# sa_dsp.net
KiCad netlist of a schematic drawn in EAGLE
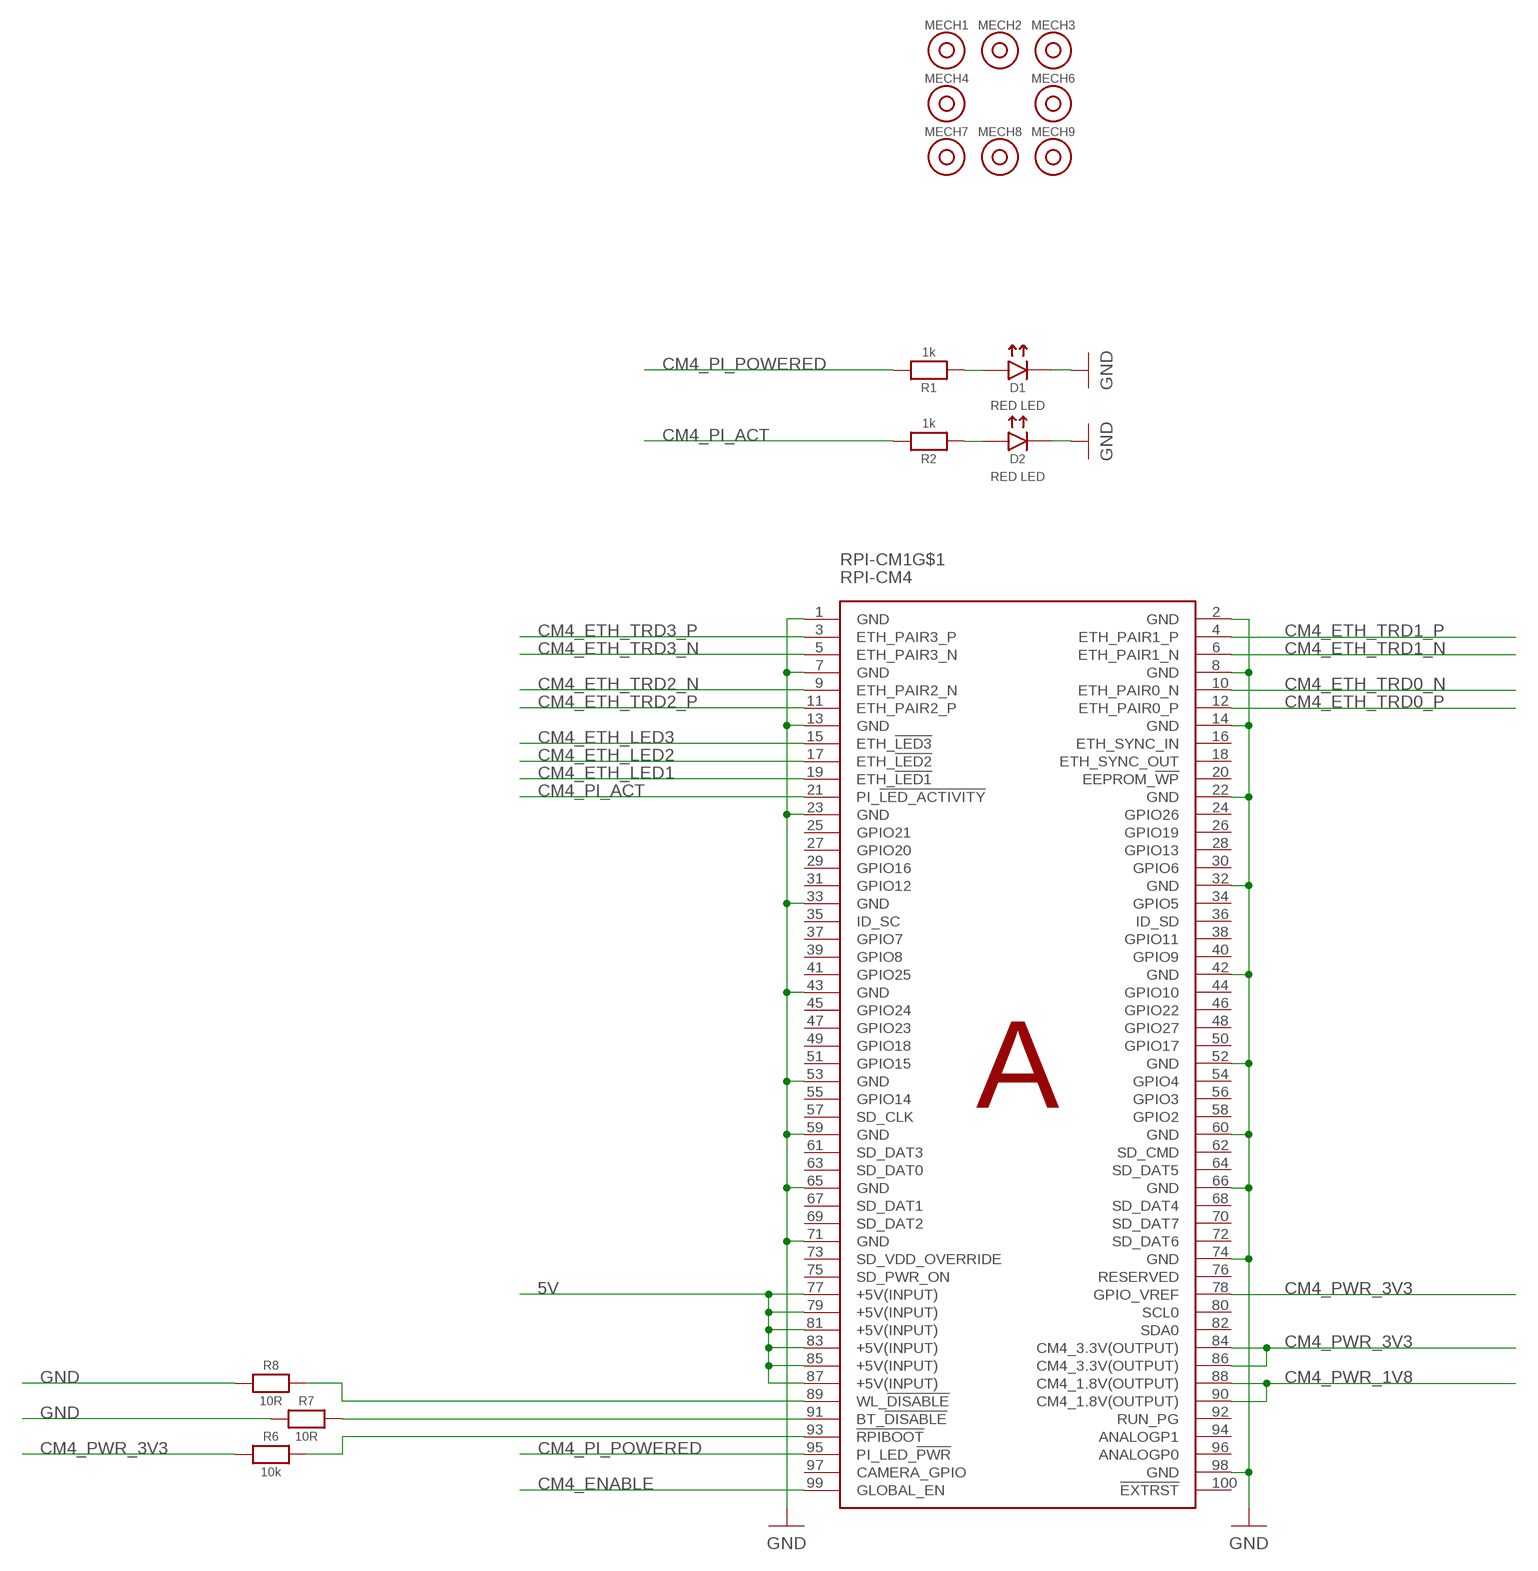
[diagram p0: schematic, sheet 1, part 1 of 2]
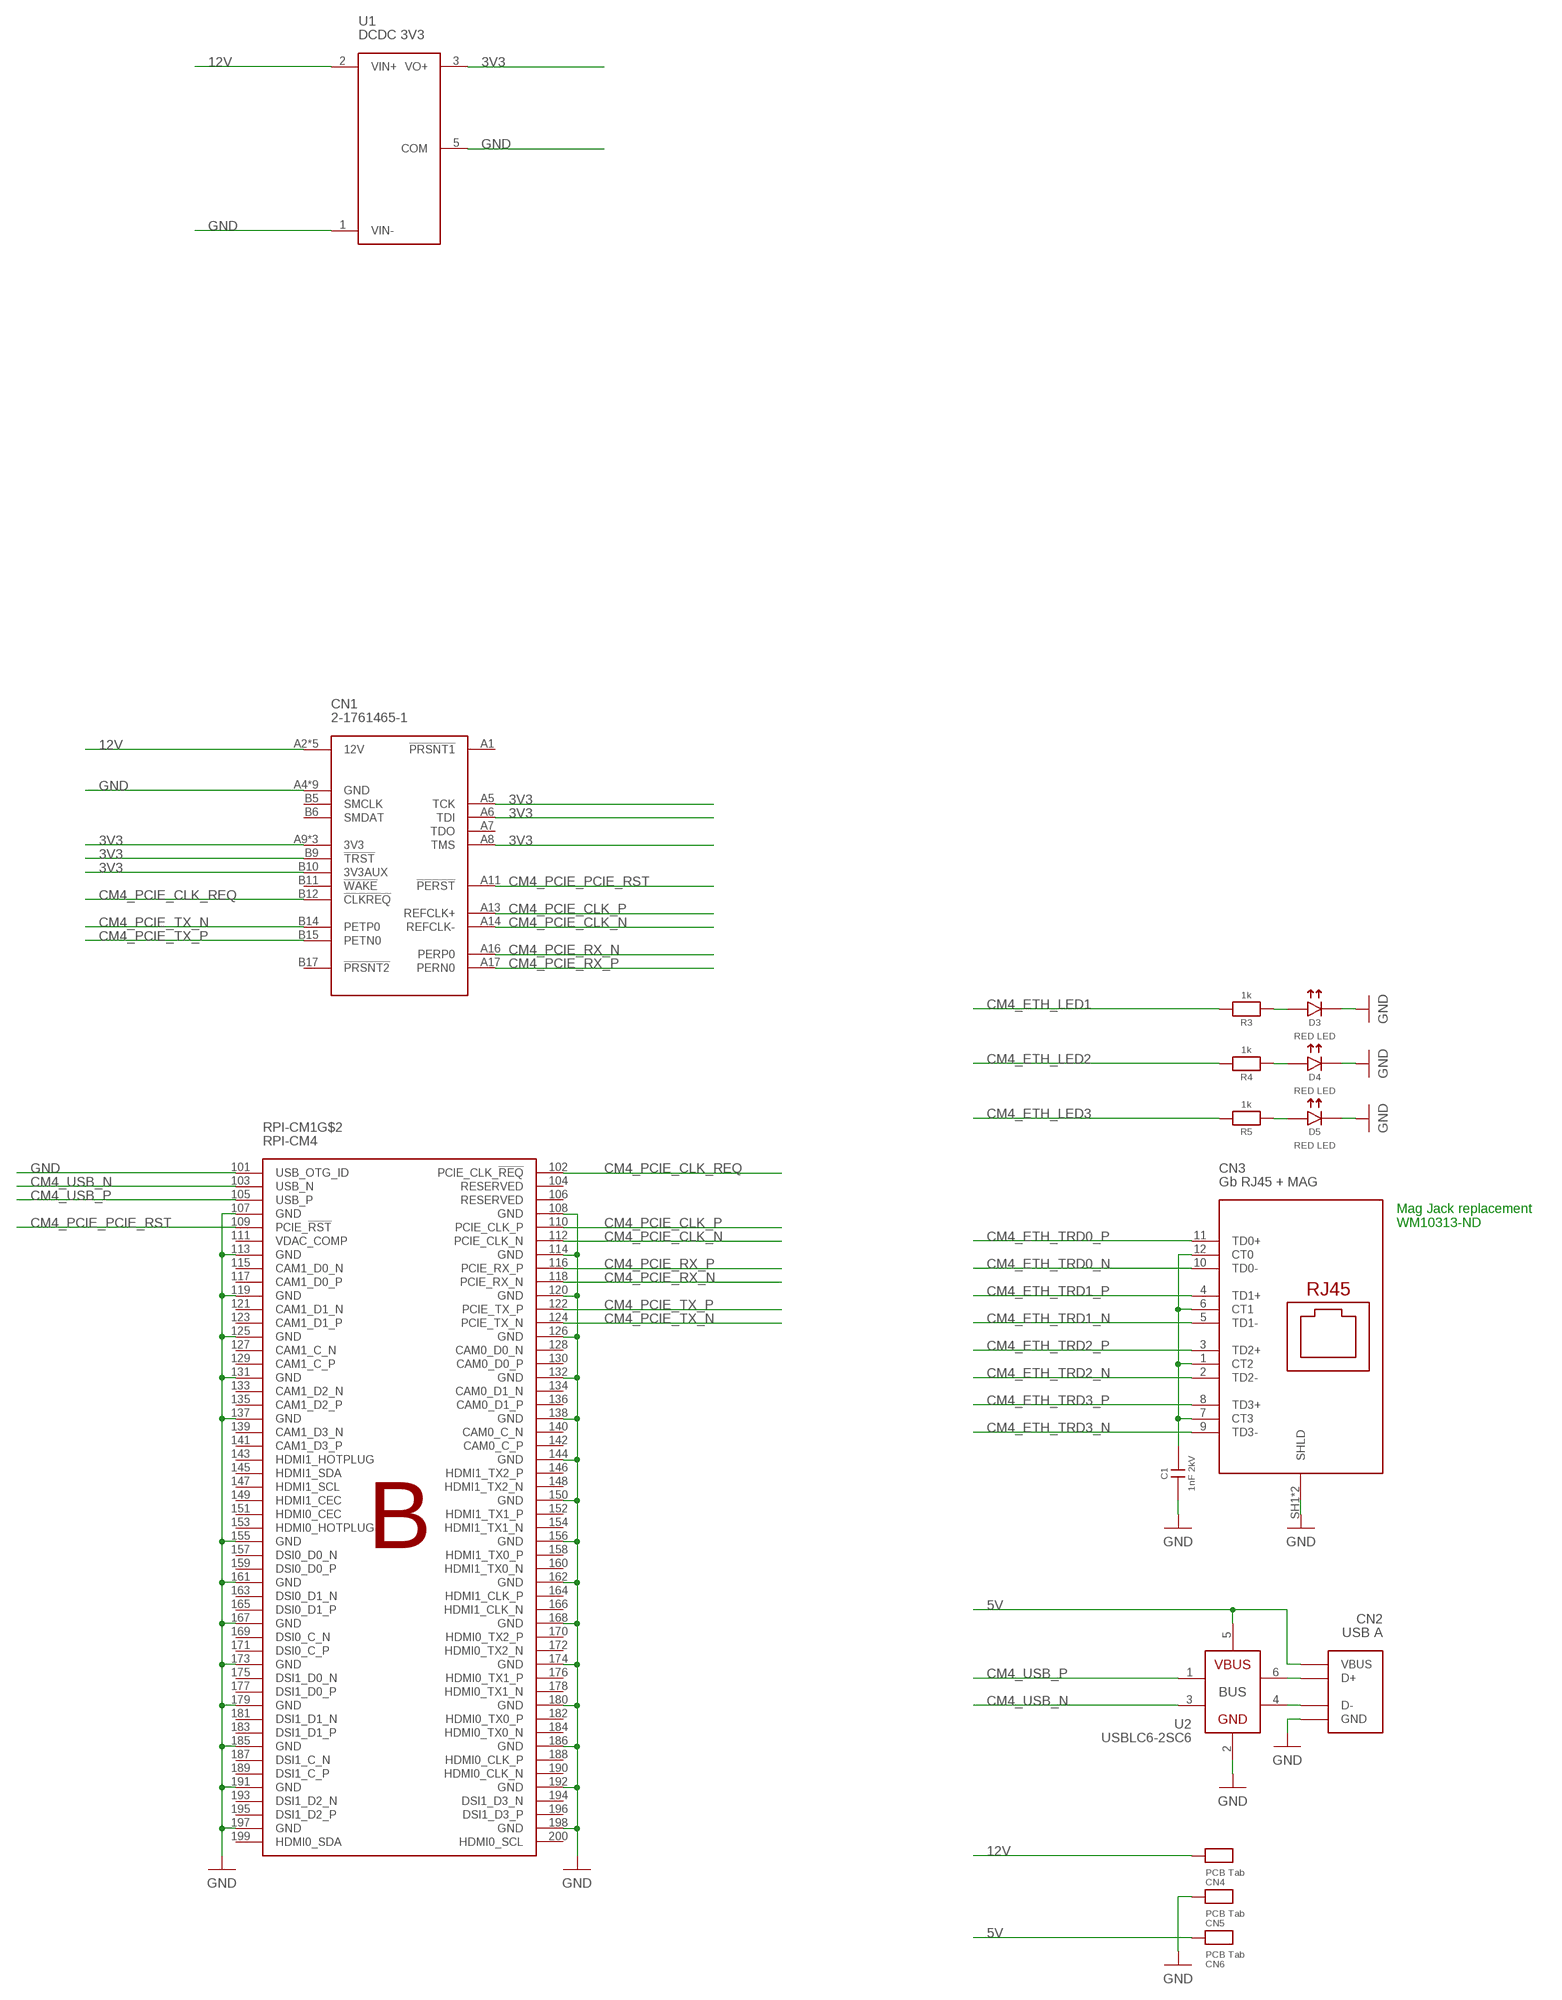
[diagram p1: schematic, sheet 1, part 2 of 2]

(export (version "E")
  (design (tool "Eeschema 10.0.6"))
  (components
    (comp (ref "C1")
      (value "1nF 2kV")
      (footprint "eagle-import:1812")
      (libsource (lib "eagle-import") (part "C1812C102KGRACAUTO"))
    )
    (comp (ref "CN1")
      (value "2-1761465-1")
      (footprint "eagle-import:CONN36_2-1761465-1_TEC")
      (libsource (lib "eagle-import") (part "2-1761465-1"))
    )
    (comp (ref "CN2")
      (value "USB A")
      (footprint "eagle-import:629104190121")
      (libsource (lib "eagle-import") (part "629104190121"))
    )
    (comp (ref "CN3")
      (value "Gb RJ45 + MAG")
      (footprint "eagle-import:0857931020")
      (libsource (lib "eagle-import") (part "0857931020"))
    )
    (comp (ref "CN4")
      (value "PCB Tab")
      (footprint "eagle-import:PCB_TAB_SMALL")
      (libsource (lib "eagle-import") (part "PCB_TAB_SMALL"))
    )
    (comp (ref "CN5")
      (value "PCB Tab")
      (footprint "eagle-import:PCB_TAB_SMALL")
      (libsource (lib "eagle-import") (part "PCB_TAB_SMALL"))
    )
    (comp (ref "CN6")
      (value "PCB Tab")
      (footprint "eagle-import:PCB_TAB_SMALL")
      (libsource (lib "eagle-import") (part "PCB_TAB_SMALL"))
    )
    (comp (ref "D1")
      (value "RED LED")
      (footprint "eagle-import:0603_POLAR")
      (libsource (lib "eagle-import") (part "150060RS75000"))
    )
    (comp (ref "D2")
      (value "RED LED")
      (footprint "eagle-import:0603_POLAR")
      (libsource (lib "eagle-import") (part "150060RS75000"))
    )
    (comp (ref "D3")
      (value "RED LED")
      (footprint "eagle-import:0603_POLAR")
      (libsource (lib "eagle-import") (part "150060RS75000"))
    )
    (comp (ref "D4")
      (value "RED LED")
      (footprint "eagle-import:0603_POLAR")
      (libsource (lib "eagle-import") (part "150060RS75000"))
    )
    (comp (ref "D5")
      (value "RED LED")
      (footprint "eagle-import:0603_POLAR")
      (libsource (lib "eagle-import") (part "150060RS75000"))
    )
    (comp (ref "MECH1")
      (value "6mm x 3mm")
      (footprint "eagle-import:MOUNTHOLE_6X3")
      (libsource (lib "eagle-import") (part "MOUNTHOLE"))
    )
    (comp (ref "MECH2")
      (value "6mm x 3mm")
      (footprint "eagle-import:MOUNTHOLE_6X3")
      (libsource (lib "eagle-import") (part "MOUNTHOLE"))
    )
    (comp (ref "MECH3")
      (value "6mm x 3mm")
      (footprint "eagle-import:MOUNTHOLE_6X3")
      (libsource (lib "eagle-import") (part "MOUNTHOLE"))
    )
    (comp (ref "MECH4")
      (value "6mm x 3mm")
      (footprint "eagle-import:MOUNTHOLE_6X3")
      (libsource (lib "eagle-import") (part "MOUNTHOLE"))
    )
    (comp (ref "MECH6")
      (value "6mm x 3mm")
      (footprint "eagle-import:MOUNTHOLE_6X3")
      (libsource (lib "eagle-import") (part "MOUNTHOLE"))
    )
    (comp (ref "MECH7")
      (value "6mm x 3mm")
      (footprint "eagle-import:MOUNTHOLE_6X3")
      (libsource (lib "eagle-import") (part "MOUNTHOLE"))
    )
    (comp (ref "MECH8")
      (value "6mm x 3mm")
      (footprint "eagle-import:MOUNTHOLE_6X3")
      (libsource (lib "eagle-import") (part "MOUNTHOLE"))
    )
    (comp (ref "MECH9")
      (value "6mm x 3mm")
      (footprint "eagle-import:MOUNTHOLE_6X3")
      (libsource (lib "eagle-import") (part "MOUNTHOLE"))
    )
    (comp (ref "R1")
      (value "1k")
      (footprint "eagle-import:0603")
      (fields
        (field (name "MANUFACTURER") "Vishay Dale")
        (field (name "POWER") "0.1W, 1/10W")
        (field (name "TOLERANCE") "±1%")
      )
      (libsource (lib "eagle-import") (part "CRCW06031K00FKEB"))
    )
    (comp (ref "R2")
      (value "1k")
      (footprint "eagle-import:0603")
      (fields
        (field (name "MANUFACTURER") "Vishay Dale")
        (field (name "POWER") "0.1W, 1/10W")
        (field (name "TOLERANCE") "±1%")
      )
      (libsource (lib "eagle-import") (part "CRCW06031K00FKEB"))
    )
    (comp (ref "R3")
      (value "1k")
      (footprint "eagle-import:0603")
      (fields
        (field (name "MANUFACTURER") "Vishay Dale")
        (field (name "POWER") "0.1W, 1/10W")
        (field (name "TOLERANCE") "±1%")
      )
      (libsource (lib "eagle-import") (part "CRCW06031K00FKEB"))
    )
    (comp (ref "R4")
      (value "1k")
      (footprint "eagle-import:0603")
      (fields
        (field (name "MANUFACTURER") "Vishay Dale")
        (field (name "POWER") "0.1W, 1/10W")
        (field (name "TOLERANCE") "±1%")
      )
      (libsource (lib "eagle-import") (part "CRCW06031K00FKEB"))
    )
    (comp (ref "R5")
      (value "1k")
      (footprint "eagle-import:0603")
      (fields
        (field (name "MANUFACTURER") "Vishay Dale")
        (field (name "POWER") "0.1W, 1/10W")
        (field (name "TOLERANCE") "±1%")
      )
      (libsource (lib "eagle-import") (part "CRCW06031K00FKEB"))
    )
    (comp (ref "R6")
      (value "10k")
      (footprint "eagle-import:0603")
      (fields
        (field (name "MANUFACTURER") "Vishay Dale")
        (field (name "POWER") "0.1W, 1/10W")
        (field (name "TOLERANCE") "±1%")
      )
      (libsource (lib "eagle-import") (part "CRCW060310K0FKTA"))
    )
    (comp (ref "R7")
      (value "10R")
      (footprint "eagle-import:0603")
      (fields
        (field (name "MANUFACTURER") "Vishay Dale")
        (field (name "POWER") "0.1W, 1/10W")
        (field (name "TOLERANCE") "±1%")
      )
      (libsource (lib "eagle-import") (part "CRCW060310R0FKTA"))
    )
    (comp (ref "R8")
      (value "10R")
      (footprint "eagle-import:0603")
      (fields
        (field (name "MANUFACTURER") "Vishay Dale")
        (field (name "POWER") "0.1W, 1/10W")
        (field (name "TOLERANCE") "±1%")
      )
      (libsource (lib "eagle-import") (part "CRCW060310R0FKTA"))
    )
    (comp (ref "RPI-CM1")
      (value "RPI-CM4")
      (footprint "eagle-import:RPI-CM4")
      (libsource (lib "eagle-import") (part "RPI-CM4"))
    )
    (comp (ref "U1")
      (value "DCDC 3V3")
      (footprint "eagle-import:PDQE10")
      (libsource (lib "eagle-import") (part "PDQE15-Q24-S3-D"))
    )
    (comp (ref "U2")
      (value "USBLC6-2SC6")
      (footprint "eagle-import:SOT23-6")
      (libsource (lib "eagle-import") (part "USBLC6-2SC6"))
    )
  )
  (nets
    (net (code "1") (name "/3V3") (class "Default")
      (node (ref "CN1") (pin "A10") (pinfunction "3V3_A10") (pintype "passive"))
      (node (ref "CN1") (pin "A5") (pinfunction "TCK_A5") (pintype "passive"))
      (node (ref "CN1") (pin "A6") (pinfunction "TDI_A6") (pintype "passive"))
      (node (ref "CN1") (pin "A8") (pinfunction "TMS_A8") (pintype "passive"))
      (node (ref "CN1") (pin "A9") (pinfunction "3V3_A9") (pintype "passive"))
      (node (ref "CN1") (pin "B10") (pinfunction "3V3AUX_B10") (pintype "passive"))
      (node (ref "CN1") (pin "B8") (pinfunction "3V3_B8") (pintype "passive"))
      (node (ref "CN1") (pin "B9") (pinfunction "~{TRST}_B9") (pintype "passive"))
      (node (ref "U1") (pin "3") (pinfunction "VO+_3") (pintype "bidirectional"))
    )
    (net (code "2") (name "/5V") (class "Default")
      (node (ref "CN2") (pin "1") (pinfunction "VBUS_1") (pintype "bidirectional"))
      (node (ref "CN6") (pin "1") (pinfunction "1_1") (pintype "bidirectional"))
      (node (ref "RPI-CM1") (pin "77") (pinfunction "+5V(INPUT)_77") (pintype "passive"))
      (node (ref "RPI-CM1") (pin "79") (pinfunction "+5V(INPUT)_79") (pintype "passive"))
      (node (ref "RPI-CM1") (pin "81") (pinfunction "+5V(INPUT)_81") (pintype "passive"))
      (node (ref "RPI-CM1") (pin "83") (pinfunction "+5V(INPUT)_83") (pintype "passive"))
      (node (ref "RPI-CM1") (pin "85") (pinfunction "+5V(INPUT)_85") (pintype "passive"))
      (node (ref "RPI-CM1") (pin "87") (pinfunction "+5V(INPUT)_87") (pintype "passive"))
      (node (ref "U2") (pin "5") (pinfunction "VBUS_5") (pintype "bidirectional"))
    )
    (net (code "3") (name "/12V") (class "Default")
      (node (ref "CN1") (pin "A2") (pinfunction "12V_A2") (pintype "passive"))
      (node (ref "CN1") (pin "A3") (pinfunction "12V_A3") (pintype "passive"))
      (node (ref "CN1") (pin "B1") (pinfunction "12V_B1") (pintype "passive"))
      (node (ref "CN1") (pin "B2") (pinfunction "12V_B2") (pintype "passive"))
      (node (ref "CN1") (pin "B3") (pinfunction "12V_B3") (pintype "passive"))
      (node (ref "CN4") (pin "1") (pinfunction "1_1") (pintype "bidirectional"))
      (node (ref "U1") (pin "2") (pinfunction "VIN+_2") (pintype "bidirectional"))
    )
    (net (code "4") (name "/CM4_ENABLE") (class "Default")
      (node (ref "RPI-CM1") (pin "99") (pinfunction "GLOBAL_EN_99") (pintype "passive"))
    )
    (net (code "5") (name "/CM4_ETH_LED1") (class "Default")
      (node (ref "R3") (pin "2") (pinfunction "2_2") (pintype "bidirectional"))
      (node (ref "RPI-CM1") (pin "19") (pinfunction "ETH_~{LED1}_19") (pintype "passive"))
    )
    (net (code "6") (name "/CM4_ETH_LED2") (class "Default")
      (node (ref "R4") (pin "2") (pinfunction "2_2") (pintype "bidirectional"))
      (node (ref "RPI-CM1") (pin "17") (pinfunction "ETH_~{LED2}_17") (pintype "passive"))
    )
    (net (code "7") (name "/CM4_ETH_LED3") (class "Default")
      (node (ref "R5") (pin "2") (pinfunction "2_2") (pintype "bidirectional"))
      (node (ref "RPI-CM1") (pin "15") (pinfunction "ETH_~{LED3}_15") (pintype "passive"))
    )
    (net (code "8") (name "/CM4_ETH_TRD0_N") (class "Default")
      (node (ref "CN3") (pin "10") (pinfunction "TD0-_10") (pintype "bidirectional"))
      (node (ref "RPI-CM1") (pin "10") (pinfunction "ETH_PAIR0_N_10") (pintype "passive"))
    )
    (net (code "9") (name "/CM4_ETH_TRD0_P") (class "Default")
      (node (ref "CN3") (pin "11") (pinfunction "TD0+_11") (pintype "bidirectional"))
      (node (ref "RPI-CM1") (pin "12") (pinfunction "ETH_PAIR0_P_12") (pintype "passive"))
    )
    (net (code "10") (name "/CM4_ETH_TRD1_N") (class "Default")
      (node (ref "CN3") (pin "5") (pinfunction "TD1-_5") (pintype "bidirectional"))
      (node (ref "RPI-CM1") (pin "6") (pinfunction "ETH_PAIR1_N_6") (pintype "passive"))
    )
    (net (code "11") (name "/CM4_ETH_TRD1_P") (class "Default")
      (node (ref "CN3") (pin "4") (pinfunction "TD1+_4") (pintype "bidirectional"))
      (node (ref "RPI-CM1") (pin "4") (pinfunction "ETH_PAIR1_P_4") (pintype "passive"))
    )
    (net (code "12") (name "/CM4_ETH_TRD2_N") (class "Default")
      (node (ref "CN3") (pin "2") (pinfunction "TD2-_2") (pintype "bidirectional"))
      (node (ref "RPI-CM1") (pin "9") (pinfunction "ETH_PAIR2_N_9") (pintype "passive"))
    )
    (net (code "13") (name "/CM4_ETH_TRD2_P") (class "Default")
      (node (ref "CN3") (pin "3") (pinfunction "TD2+_3") (pintype "bidirectional"))
      (node (ref "RPI-CM1") (pin "11") (pinfunction "ETH_PAIR2_P_11") (pintype "passive"))
    )
    (net (code "14") (name "/CM4_ETH_TRD3_N") (class "Default")
      (node (ref "CN3") (pin "9") (pinfunction "TD3-_9") (pintype "bidirectional"))
      (node (ref "RPI-CM1") (pin "5") (pinfunction "ETH_PAIR3_N_5") (pintype "passive"))
    )
    (net (code "15") (name "/CM4_ETH_TRD3_P") (class "Default")
      (node (ref "CN3") (pin "8") (pinfunction "TD3+_8") (pintype "bidirectional"))
      (node (ref "RPI-CM1") (pin "3") (pinfunction "ETH_PAIR3_P_3") (pintype "passive"))
    )
    (net (code "16") (name "/CM4_PCIE_CLK_N") (class "Default")
      (node (ref "CN1") (pin "A14") (pinfunction "REFCLK-_A14") (pintype "passive"))
      (node (ref "RPI-CM1") (pin "112") (pinfunction "PCIE_CLK_N_112") (pintype "passive"))
    )
    (net (code "17") (name "/CM4_PCIE_CLK_P") (class "Default")
      (node (ref "CN1") (pin "A13") (pinfunction "REFCLK+_A13") (pintype "passive"))
      (node (ref "RPI-CM1") (pin "110") (pinfunction "PCIE_CLK_P_110") (pintype "passive"))
    )
    (net (code "18") (name "/CM4_PCIE_CLK_REQ") (class "Default")
      (node (ref "CN1") (pin "B12") (pinfunction "~{CLKREQ}_B12") (pintype "passive"))
      (node (ref "RPI-CM1") (pin "102") (pinfunction "PCIE_CLK_~{REQ}_102") (pintype "passive"))
    )
    (net (code "19") (name "/CM4_PCIE_PCIE_RST") (class "Default")
      (node (ref "CN1") (pin "A11") (pinfunction "~{PERST}_A11") (pintype "passive"))
      (node (ref "RPI-CM1") (pin "109") (pinfunction "PCIE_~{RST}_109") (pintype "passive"))
    )
    (net (code "20") (name "/CM4_PCIE_RX_N") (class "Default")
      (node (ref "CN1") (pin "A16") (pinfunction "PERP0_A16") (pintype "passive"))
      (node (ref "RPI-CM1") (pin "118") (pinfunction "PCIE_RX_N_118") (pintype "passive"))
    )
    (net (code "21") (name "/CM4_PCIE_RX_P") (class "Default")
      (node (ref "CN1") (pin "A17") (pinfunction "PERN0_A17") (pintype "passive"))
      (node (ref "RPI-CM1") (pin "116") (pinfunction "PCIE_RX_P_116") (pintype "passive"))
    )
    (net (code "22") (name "/CM4_PCIE_TX_N") (class "Default")
      (node (ref "CN1") (pin "B14") (pinfunction "PETP0_B14") (pintype "passive"))
      (node (ref "RPI-CM1") (pin "124") (pinfunction "PCIE_TX_N_124") (pintype "passive"))
    )
    (net (code "23") (name "/CM4_PCIE_TX_P") (class "Default")
      (node (ref "CN1") (pin "B15") (pinfunction "PETN0_B15") (pintype "passive"))
      (node (ref "RPI-CM1") (pin "122") (pinfunction "PCIE_TX_P_122") (pintype "passive"))
    )
    (net (code "24") (name "/CM4_PI_ACT") (class "Default")
      (node (ref "R2") (pin "2") (pinfunction "2_2") (pintype "bidirectional"))
      (node (ref "RPI-CM1") (pin "21") (pinfunction "PI_~{LED_ACTIVITY}_21") (pintype "passive"))
    )
    (net (code "25") (name "/CM4_PI_POWERED") (class "Default")
      (node (ref "R1") (pin "2") (pinfunction "2_2") (pintype "bidirectional"))
      (node (ref "RPI-CM1") (pin "95") (pinfunction "PI_LED_~{PWR}_95") (pintype "passive"))
    )
    (net (code "26") (name "/CM4_PWR_1V8") (class "Default")
      (node (ref "RPI-CM1") (pin "88") (pinfunction "CM4_1.8V(OUTPUT)_88") (pintype "passive"))
      (node (ref "RPI-CM1") (pin "90") (pinfunction "CM4_1.8V(OUTPUT)_90") (pintype "passive"))
    )
    (net (code "27") (name "/CM4_PWR_3V3") (class "Default")
      (node (ref "R6") (pin "1") (pinfunction "1_1") (pintype "bidirectional"))
      (node (ref "RPI-CM1") (pin "78") (pinfunction "GPIO_VREF_78") (pintype "passive"))
      (node (ref "RPI-CM1") (pin "84") (pinfunction "CM4_3.3V(OUTPUT)_84") (pintype "passive"))
      (node (ref "RPI-CM1") (pin "86") (pinfunction "CM4_3.3V(OUTPUT)_86") (pintype "passive"))
    )
    (net (code "28") (name "/CM4_USB_N") (class "Default")
      (node (ref "RPI-CM1") (pin "103") (pinfunction "USB_N_103") (pintype "passive"))
      (node (ref "U2") (pin "3") (pinfunction "D-_IN_3") (pintype "bidirectional"))
    )
    (net (code "29") (name "/CM4_USB_P") (class "Default")
      (node (ref "RPI-CM1") (pin "105") (pinfunction "USB_P_105") (pintype "passive"))
      (node (ref "U2") (pin "1") (pinfunction "D+_IN_1") (pintype "bidirectional"))
    )
    (net (code "30") (name "GND") (class "Default")
      (node (ref "C1") (pin "1") (pinfunction "1_1") (pintype "bidirectional"))
      (node (ref "CN1") (pin "A12") (pinfunction "GND_A12") (pintype "passive"))
      (node (ref "CN1") (pin "A15") (pinfunction "GND_A15") (pintype "passive"))
      (node (ref "CN1") (pin "A18") (pinfunction "GND_A18") (pintype "passive"))
      (node (ref "CN1") (pin "A4") (pinfunction "GND_A4") (pintype "passive"))
      (node (ref "CN1") (pin "B13") (pinfunction "GND_B13") (pintype "passive"))
      (node (ref "CN1") (pin "B16") (pinfunction "GND_B16") (pintype "passive"))
      (node (ref "CN1") (pin "B18") (pinfunction "GND_B18") (pintype "passive"))
      (node (ref "CN1") (pin "B4") (pinfunction "GND_B4") (pintype "passive"))
      (node (ref "CN1") (pin "B7") (pinfunction "GND_B7") (pintype "passive"))
      (node (ref "CN2") (pin "4") (pinfunction "GND_4") (pintype "bidirectional"))
      (node (ref "CN2") (pin "SH1") (pinfunction "GND_SH1") (pintype "bidirectional"))
      (node (ref "CN2") (pin "SH2") (pinfunction "GND_SH2") (pintype "bidirectional"))
      (node (ref "CN2") (pin "SH3") (pinfunction "GND_SH3") (pintype "bidirectional"))
      (node (ref "CN2") (pin "SH4") (pinfunction "GND_SH4") (pintype "bidirectional"))
      (node (ref "CN3") (pin "SH1") (pinfunction "SHLD_SH1") (pintype "bidirectional"))
      (node (ref "CN3") (pin "SH2") (pinfunction "SHLD_SH2") (pintype "bidirectional"))
      (node (ref "CN5") (pin "1") (pinfunction "1_1") (pintype "bidirectional"))
      (node (ref "D1") (pin "K") (pinfunction "K_K") (pintype "bidirectional"))
      (node (ref "D2") (pin "K") (pinfunction "K_K") (pintype "bidirectional"))
      (node (ref "D3") (pin "K") (pinfunction "K_K") (pintype "bidirectional"))
      (node (ref "D4") (pin "K") (pinfunction "K_K") (pintype "bidirectional"))
      (node (ref "D5") (pin "K") (pinfunction "K_K") (pintype "bidirectional"))
      (node (ref "R7") (pin "1") (pinfunction "1_1") (pintype "bidirectional"))
      (node (ref "R8") (pin "1") (pinfunction "1_1") (pintype "bidirectional"))
      (node (ref "RPI-CM1") (pin "1") (pinfunction "GND_1") (pintype "passive"))
      (node (ref "RPI-CM1") (pin "101") (pinfunction "USB_OTG_ID_101") (pintype "passive"))
      (node (ref "RPI-CM1") (pin "107") (pinfunction "GND_107") (pintype "passive"))
      (node (ref "RPI-CM1") (pin "108") (pinfunction "GND_108") (pintype "passive"))
      (node (ref "RPI-CM1") (pin "113") (pinfunction "GND_113") (pintype "passive"))
      (node (ref "RPI-CM1") (pin "114") (pinfunction "GND_114") (pintype "passive"))
      (node (ref "RPI-CM1") (pin "119") (pinfunction "GND_119") (pintype "passive"))
      (node (ref "RPI-CM1") (pin "120") (pinfunction "GND_120") (pintype "passive"))
      (node (ref "RPI-CM1") (pin "125") (pinfunction "GND_125") (pintype "passive"))
      (node (ref "RPI-CM1") (pin "126") (pinfunction "GND_126") (pintype "passive"))
      (node (ref "RPI-CM1") (pin "13") (pinfunction "GND_13") (pintype "passive"))
      (node (ref "RPI-CM1") (pin "131") (pinfunction "GND_131") (pintype "passive"))
      (node (ref "RPI-CM1") (pin "132") (pinfunction "GND_132") (pintype "passive"))
      (node (ref "RPI-CM1") (pin "137") (pinfunction "GND_137") (pintype "passive"))
      (node (ref "RPI-CM1") (pin "138") (pinfunction "GND_138") (pintype "passive"))
      (node (ref "RPI-CM1") (pin "14") (pinfunction "GND_14") (pintype "passive"))
      (node (ref "RPI-CM1") (pin "144") (pinfunction "GND_144") (pintype "passive"))
      (node (ref "RPI-CM1") (pin "150") (pinfunction "GND_150") (pintype "passive"))
      (node (ref "RPI-CM1") (pin "155") (pinfunction "GND_155") (pintype "passive"))
      (node (ref "RPI-CM1") (pin "156") (pinfunction "GND_156") (pintype "passive"))
      (node (ref "RPI-CM1") (pin "161") (pinfunction "GND_161") (pintype "passive"))
      (node (ref "RPI-CM1") (pin "162") (pinfunction "GND_162") (pintype "passive"))
      (node (ref "RPI-CM1") (pin "167") (pinfunction "GND_167") (pintype "passive"))
      (node (ref "RPI-CM1") (pin "168") (pinfunction "GND_168") (pintype "passive"))
      (node (ref "RPI-CM1") (pin "173") (pinfunction "GND_173") (pintype "passive"))
      (node (ref "RPI-CM1") (pin "174") (pinfunction "GND_174") (pintype "passive"))
      (node (ref "RPI-CM1") (pin "179") (pinfunction "GND_179") (pintype "passive"))
      (node (ref "RPI-CM1") (pin "180") (pinfunction "GND_180") (pintype "passive"))
      (node (ref "RPI-CM1") (pin "185") (pinfunction "GND_185") (pintype "passive"))
      (node (ref "RPI-CM1") (pin "186") (pinfunction "GND_186") (pintype "passive"))
      (node (ref "RPI-CM1") (pin "191") (pinfunction "GND_191") (pintype "passive"))
      (node (ref "RPI-CM1") (pin "192") (pinfunction "GND_192") (pintype "passive"))
      (node (ref "RPI-CM1") (pin "197") (pinfunction "GND_197") (pintype "passive"))
      (node (ref "RPI-CM1") (pin "198") (pinfunction "GND_198") (pintype "passive"))
      (node (ref "RPI-CM1") (pin "2") (pinfunction "GND_2") (pintype "passive"))
      (node (ref "RPI-CM1") (pin "22") (pinfunction "GND_22") (pintype "passive"))
      (node (ref "RPI-CM1") (pin "23") (pinfunction "GND_23") (pintype "passive"))
      (node (ref "RPI-CM1") (pin "32") (pinfunction "GND_32") (pintype "passive"))
      (node (ref "RPI-CM1") (pin "33") (pinfunction "GND_33") (pintype "passive"))
      (node (ref "RPI-CM1") (pin "42") (pinfunction "GND_42") (pintype "passive"))
      (node (ref "RPI-CM1") (pin "43") (pinfunction "GND_43") (pintype "passive"))
      (node (ref "RPI-CM1") (pin "52") (pinfunction "GND_52") (pintype "passive"))
      (node (ref "RPI-CM1") (pin "53") (pinfunction "GND_53") (pintype "passive"))
      (node (ref "RPI-CM1") (pin "59") (pinfunction "GND_59") (pintype "passive"))
      (node (ref "RPI-CM1") (pin "60") (pinfunction "GND_60") (pintype "passive"))
      (node (ref "RPI-CM1") (pin "65") (pinfunction "GND_65") (pintype "passive"))
      (node (ref "RPI-CM1") (pin "66") (pinfunction "GND_66") (pintype "passive"))
      (node (ref "RPI-CM1") (pin "7") (pinfunction "GND_7") (pintype "passive"))
      (node (ref "RPI-CM1") (pin "71") (pinfunction "GND_71") (pintype "passive"))
      (node (ref "RPI-CM1") (pin "74") (pinfunction "GND_74") (pintype "passive"))
      (node (ref "RPI-CM1") (pin "8") (pinfunction "GND_8") (pintype "passive"))
      (node (ref "RPI-CM1") (pin "98") (pinfunction "GND_98") (pintype "passive"))
      (node (ref "U1") (pin "1") (pinfunction "VIN-_1") (pintype "bidirectional"))
      (node (ref "U1") (pin "5") (pinfunction "COM_5") (pintype "bidirectional"))
      (node (ref "U2") (pin "2") (pinfunction "GND_2") (pintype "bidirectional"))
    )
    (net (code "31") (name "Net-(CN2-D+)") (class "Default")
      (node (ref "CN2") (pin "3") (pinfunction "D+_3") (pintype "bidirectional"))
      (node (ref "U2") (pin "6") (pinfunction "D+_OUT_6") (pintype "bidirectional"))
    )
    (net (code "32") (name "Net-(CN2-D-)") (class "Default")
      (node (ref "CN2") (pin "2") (pinfunction "D-_2") (pintype "bidirectional"))
      (node (ref "U2") (pin "4") (pinfunction "D-OUT_4") (pintype "bidirectional"))
    )
    (net (code "33") (name "Net-(CN3-CT0)") (class "Default")
      (node (ref "C1") (pin "2") (pinfunction "2_2") (pintype "bidirectional"))
      (node (ref "CN3") (pin "1") (pinfunction "CT2_1") (pintype "bidirectional"))
      (node (ref "CN3") (pin "12") (pinfunction "CT0_12") (pintype "bidirectional"))
      (node (ref "CN3") (pin "6") (pinfunction "CT1_6") (pintype "bidirectional"))
      (node (ref "CN3") (pin "7") (pinfunction "CT3_7") (pintype "bidirectional"))
    )
    (net (code "34") (name "Net-(D1-PadA)") (class "Default")
      (node (ref "D1") (pin "A") (pinfunction "A_A") (pintype "bidirectional"))
      (node (ref "R1") (pin "1") (pinfunction "1_1") (pintype "bidirectional"))
    )
    (net (code "35") (name "Net-(D2-PadA)") (class "Default")
      (node (ref "D2") (pin "A") (pinfunction "A_A") (pintype "bidirectional"))
      (node (ref "R2") (pin "1") (pinfunction "1_1") (pintype "bidirectional"))
    )
    (net (code "36") (name "Net-(D3-PadA)") (class "Default")
      (node (ref "D3") (pin "A") (pinfunction "A_A") (pintype "bidirectional"))
      (node (ref "R3") (pin "1") (pinfunction "1_1") (pintype "bidirectional"))
    )
    (net (code "37") (name "Net-(D4-PadA)") (class "Default")
      (node (ref "D4") (pin "A") (pinfunction "A_A") (pintype "bidirectional"))
      (node (ref "R4") (pin "1") (pinfunction "1_1") (pintype "bidirectional"))
    )
    (net (code "38") (name "Net-(D5-PadA)") (class "Default")
      (node (ref "D5") (pin "A") (pinfunction "A_A") (pintype "bidirectional"))
      (node (ref "R5") (pin "1") (pinfunction "1_1") (pintype "bidirectional"))
    )
    (net (code "39") (name "Net-(RPI-CM1A-BT_~{DISABLE})") (class "Default")
      (node (ref "R7") (pin "2") (pinfunction "2_2") (pintype "bidirectional"))
      (node (ref "RPI-CM1") (pin "91") (pinfunction "BT_~{DISABLE}_91") (pintype "passive"))
    )
    (net (code "40") (name "Net-(RPI-CM1A-WL_~{DISABLE})") (class "Default")
      (node (ref "R8") (pin "2") (pinfunction "2_2") (pintype "bidirectional"))
      (node (ref "RPI-CM1") (pin "89") (pinfunction "WL_~{DISABLE}_89") (pintype "passive"))
    )
    (net (code "41") (name "Net-(RPI-CM1A-~{RPIBOOT})") (class "Default")
      (node (ref "R6") (pin "2") (pinfunction "2_2") (pintype "bidirectional"))
      (node (ref "RPI-CM1") (pin "93") (pinfunction "~{RPIBOOT}_93") (pintype "passive"))
    )
    (net (code "42") (name "unconnected-(CN1-SMCLK-PadB5)") (class "Default")
      (node (ref "CN1") (pin "B5") (pinfunction "SMCLK_B5") (pintype "passive"))
    )
    (net (code "43") (name "unconnected-(CN1-SMDAT-PadB6)") (class "Default")
      (node (ref "CN1") (pin "B6") (pinfunction "SMDAT_B6") (pintype "passive"))
    )
    (net (code "44") (name "unconnected-(CN1-TDO-PadA7)") (class "Default")
      (node (ref "CN1") (pin "A7") (pinfunction "TDO_A7") (pintype "passive"))
    )
    (net (code "45") (name "unconnected-(CN1-~{PRSNT1}-PadA1)") (class "Default")
      (node (ref "CN1") (pin "A1") (pinfunction "~{PRSNT1}_A1") (pintype "passive"))
    )
    (net (code "46") (name "unconnected-(CN1-~{PRSNT2}-PadB17)") (class "Default")
      (node (ref "CN1") (pin "B17") (pinfunction "~{PRSNT2}_B17") (pintype "passive"))
    )
    (net (code "47") (name "unconnected-(CN1-~{WAKE}-PadB11)") (class "Default")
      (node (ref "CN1") (pin "B11") (pinfunction "~{WAKE}_B11") (pintype "passive"))
    )
    (net (code "48") (name "unconnected-(RPI-CM1A-ANALOGP0-Pad96)") (class "Default")
      (node (ref "RPI-CM1") (pin "96") (pinfunction "ANALOGP0_96") (pintype "passive"))
    )
    (net (code "49") (name "unconnected-(RPI-CM1A-ANALOGP1-Pad94)") (class "Default")
      (node (ref "RPI-CM1") (pin "94") (pinfunction "ANALOGP1_94") (pintype "passive"))
    )
    (net (code "50") (name "unconnected-(RPI-CM1A-CAMERA_GPIO-Pad97)") (class "Default")
      (node (ref "RPI-CM1") (pin "97") (pinfunction "CAMERA_GPIO_97") (pintype "passive"))
    )
    (net (code "51") (name "unconnected-(RPI-CM1A-EEPROM_~{WP}-Pad20)") (class "Default")
      (node (ref "RPI-CM1") (pin "20") (pinfunction "EEPROM_~{WP}_20") (pintype "passive"))
    )
    (net (code "52") (name "unconnected-(RPI-CM1A-ETH_SYNC_IN-Pad16)") (class "Default")
      (node (ref "RPI-CM1") (pin "16") (pinfunction "ETH_SYNC_IN_16") (pintype "passive"))
    )
    (net (code "53") (name "unconnected-(RPI-CM1A-ETH_SYNC_OUT-Pad18)") (class "Default")
      (node (ref "RPI-CM1") (pin "18") (pinfunction "ETH_SYNC_OUT_18") (pintype "passive"))
    )
    (net (code "54") (name "unconnected-(RPI-CM1A-GPIO2-Pad58)") (class "Default")
      (node (ref "RPI-CM1") (pin "58") (pinfunction "GPIO2_58") (pintype "passive"))
    )
    (net (code "55") (name "unconnected-(RPI-CM1A-GPIO3-Pad56)") (class "Default")
      (node (ref "RPI-CM1") (pin "56") (pinfunction "GPIO3_56") (pintype "passive"))
    )
    (net (code "56") (name "unconnected-(RPI-CM1A-GPIO4-Pad54)") (class "Default")
      (node (ref "RPI-CM1") (pin "54") (pinfunction "GPIO4_54") (pintype "passive"))
    )
    (net (code "57") (name "unconnected-(RPI-CM1A-GPIO5-Pad34)") (class "Default")
      (node (ref "RPI-CM1") (pin "34") (pinfunction "GPIO5_34") (pintype "passive"))
    )
    (net (code "58") (name "unconnected-(RPI-CM1A-GPIO6-Pad30)") (class "Default")
      (node (ref "RPI-CM1") (pin "30") (pinfunction "GPIO6_30") (pintype "passive"))
    )
    (net (code "59") (name "unconnected-(RPI-CM1A-GPIO7-Pad37)") (class "Default")
      (node (ref "RPI-CM1") (pin "37") (pinfunction "GPIO7_37") (pintype "passive"))
    )
    (net (code "60") (name "unconnected-(RPI-CM1A-GPIO8-Pad39)") (class "Default")
      (node (ref "RPI-CM1") (pin "39") (pinfunction "GPIO8_39") (pintype "passive"))
    )
    (net (code "61") (name "unconnected-(RPI-CM1A-GPIO9-Pad40)") (class "Default")
      (node (ref "RPI-CM1") (pin "40") (pinfunction "GPIO9_40") (pintype "passive"))
    )
    (net (code "62") (name "unconnected-(RPI-CM1A-GPIO10-Pad44)") (class "Default")
      (node (ref "RPI-CM1") (pin "44") (pinfunction "GPIO10_44") (pintype "passive"))
    )
    (net (code "63") (name "unconnected-(RPI-CM1A-GPIO11-Pad38)") (class "Default")
      (node (ref "RPI-CM1") (pin "38") (pinfunction "GPIO11_38") (pintype "passive"))
    )
    (net (code "64") (name "unconnected-(RPI-CM1A-GPIO12-Pad31)") (class "Default")
      (node (ref "RPI-CM1") (pin "31") (pinfunction "GPIO12_31") (pintype "passive"))
    )
    (net (code "65") (name "unconnected-(RPI-CM1A-GPIO13-Pad28)") (class "Default")
      (node (ref "RPI-CM1") (pin "28") (pinfunction "GPIO13_28") (pintype "passive"))
    )
    (net (code "66") (name "unconnected-(RPI-CM1A-GPIO14-Pad55)") (class "Default")
      (node (ref "RPI-CM1") (pin "55") (pinfunction "GPIO14_55") (pintype "passive"))
    )
    (net (code "67") (name "unconnected-(RPI-CM1A-GPIO15-Pad51)") (class "Default")
      (node (ref "RPI-CM1") (pin "51") (pinfunction "GPIO15_51") (pintype "passive"))
    )
    (net (code "68") (name "unconnected-(RPI-CM1A-GPIO16-Pad29)") (class "Default")
      (node (ref "RPI-CM1") (pin "29") (pinfunction "GPIO16_29") (pintype "passive"))
    )
    (net (code "69") (name "unconnected-(RPI-CM1A-GPIO17-Pad50)") (class "Default")
      (node (ref "RPI-CM1") (pin "50") (pinfunction "GPIO17_50") (pintype "passive"))
    )
    (net (code "70") (name "unconnected-(RPI-CM1A-GPIO18-Pad49)") (class "Default")
      (node (ref "RPI-CM1") (pin "49") (pinfunction "GPIO18_49") (pintype "passive"))
    )
    (net (code "71") (name "unconnected-(RPI-CM1A-GPIO19-Pad26)") (class "Default")
      (node (ref "RPI-CM1") (pin "26") (pinfunction "GPIO19_26") (pintype "passive"))
    )
    (net (code "72") (name "unconnected-(RPI-CM1A-GPIO20-Pad27)") (class "Default")
      (node (ref "RPI-CM1") (pin "27") (pinfunction "GPIO20_27") (pintype "passive"))
    )
    (net (code "73") (name "unconnected-(RPI-CM1A-GPIO21-Pad25)") (class "Default")
      (node (ref "RPI-CM1") (pin "25") (pinfunction "GPIO21_25") (pintype "passive"))
    )
    (net (code "74") (name "unconnected-(RPI-CM1A-GPIO22-Pad46)") (class "Default")
      (node (ref "RPI-CM1") (pin "46") (pinfunction "GPIO22_46") (pintype "passive"))
    )
    (net (code "75") (name "unconnected-(RPI-CM1A-GPIO23-Pad47)") (class "Default")
      (node (ref "RPI-CM1") (pin "47") (pinfunction "GPIO23_47") (pintype "passive"))
    )
    (net (code "76") (name "unconnected-(RPI-CM1A-GPIO24-Pad45)") (class "Default")
      (node (ref "RPI-CM1") (pin "45") (pinfunction "GPIO24_45") (pintype "passive"))
    )
    (net (code "77") (name "unconnected-(RPI-CM1A-GPIO25-Pad41)") (class "Default")
      (node (ref "RPI-CM1") (pin "41") (pinfunction "GPIO25_41") (pintype "passive"))
    )
    (net (code "78") (name "unconnected-(RPI-CM1A-GPIO26-Pad24)") (class "Default")
      (node (ref "RPI-CM1") (pin "24") (pinfunction "GPIO26_24") (pintype "passive"))
    )
    (net (code "79") (name "unconnected-(RPI-CM1A-GPIO27-Pad48)") (class "Default")
      (node (ref "RPI-CM1") (pin "48") (pinfunction "GPIO27_48") (pintype "passive"))
    )
    (net (code "80") (name "unconnected-(RPI-CM1A-ID_SC-Pad35)") (class "Default")
      (node (ref "RPI-CM1") (pin "35") (pinfunction "ID_SC_35") (pintype "passive"))
    )
    (net (code "81") (name "unconnected-(RPI-CM1A-ID_SD-Pad36)") (class "Default")
      (node (ref "RPI-CM1") (pin "36") (pinfunction "ID_SD_36") (pintype "passive"))
    )
    (net (code "82") (name "unconnected-(RPI-CM1A-RESERVED-Pad76)") (class "Default")
      (node (ref "RPI-CM1") (pin "76") (pinfunction "RESERVED_76") (pintype "passive"))
    )
    (net (code "83") (name "unconnected-(RPI-CM1A-RUN_PG-Pad92)") (class "Default")
      (node (ref "RPI-CM1") (pin "92") (pinfunction "RUN_PG_92") (pintype "passive"))
    )
    (net (code "84") (name "unconnected-(RPI-CM1A-SCL0-Pad80)") (class "Default")
      (node (ref "RPI-CM1") (pin "80") (pinfunction "SCL0_80") (pintype "passive"))
    )
    (net (code "85") (name "unconnected-(RPI-CM1A-SDA0-Pad82)") (class "Default")
      (node (ref "RPI-CM1") (pin "82") (pinfunction "SDA0_82") (pintype "passive"))
    )
    (net (code "86") (name "unconnected-(RPI-CM1A-SD_CLK-Pad57)") (class "Default")
      (node (ref "RPI-CM1") (pin "57") (pinfunction "SD_CLK_57") (pintype "passive"))
    )
    (net (code "87") (name "unconnected-(RPI-CM1A-SD_CMD-Pad62)") (class "Default")
      (node (ref "RPI-CM1") (pin "62") (pinfunction "SD_CMD_62") (pintype "passive"))
    )
    (net (code "88") (name "unconnected-(RPI-CM1A-SD_DAT0-Pad63)") (class "Default")
      (node (ref "RPI-CM1") (pin "63") (pinfunction "SD_DAT0_63") (pintype "passive"))
    )
    (net (code "89") (name "unconnected-(RPI-CM1A-SD_DAT1-Pad67)") (class "Default")
      (node (ref "RPI-CM1") (pin "67") (pinfunction "SD_DAT1_67") (pintype "passive"))
    )
    (net (code "90") (name "unconnected-(RPI-CM1A-SD_DAT2-Pad69)") (class "Default")
      (node (ref "RPI-CM1") (pin "69") (pinfunction "SD_DAT2_69") (pintype "passive"))
    )
    (net (code "91") (name "unconnected-(RPI-CM1A-SD_DAT3-Pad61)") (class "Default")
      (node (ref "RPI-CM1") (pin "61") (pinfunction "SD_DAT3_61") (pintype "passive"))
    )
    (net (code "92") (name "unconnected-(RPI-CM1A-SD_DAT4-Pad68)") (class "Default")
      (node (ref "RPI-CM1") (pin "68") (pinfunction "SD_DAT4_68") (pintype "passive"))
    )
    (net (code "93") (name "unconnected-(RPI-CM1A-SD_DAT5-Pad64)") (class "Default")
      (node (ref "RPI-CM1") (pin "64") (pinfunction "SD_DAT5_64") (pintype "passive"))
    )
    (net (code "94") (name "unconnected-(RPI-CM1A-SD_DAT6-Pad72)") (class "Default")
      (node (ref "RPI-CM1") (pin "72") (pinfunction "SD_DAT6_72") (pintype "passive"))
    )
    (net (code "95") (name "unconnected-(RPI-CM1A-SD_DAT7-Pad70)") (class "Default")
      (node (ref "RPI-CM1") (pin "70") (pinfunction "SD_DAT7_70") (pintype "passive"))
    )
    (net (code "96") (name "unconnected-(RPI-CM1A-SD_PWR_ON-Pad75)") (class "Default")
      (node (ref "RPI-CM1") (pin "75") (pinfunction "SD_PWR_ON_75") (pintype "passive"))
    )
    (net (code "97") (name "unconnected-(RPI-CM1A-SD_VDD_OVERRIDE-Pad73)") (class "Default")
      (node (ref "RPI-CM1") (pin "73") (pinfunction "SD_VDD_OVERRIDE_73") (pintype "passive"))
    )
    (net (code "98") (name "unconnected-(RPI-CM1A-~{EXTRST}-Pad100)") (class "Default")
      (node (ref "RPI-CM1") (pin "100") (pinfunction "~{EXTRST}_100") (pintype "passive"))
    )
    (net (code "99") (name "unconnected-(RPI-CM1B-CAM0_C_N-Pad140)") (class "Default")
      (node (ref "RPI-CM1") (pin "140") (pinfunction "CAM0_C_N_140") (pintype "passive"))
    )
    (net (code "100") (name "unconnected-(RPI-CM1B-CAM0_C_P-Pad142)") (class "Default")
      (node (ref "RPI-CM1") (pin "142") (pinfunction "CAM0_C_P_142") (pintype "passive"))
    )
    (net (code "101") (name "unconnected-(RPI-CM1B-CAM0_D0_N-Pad128)") (class "Default")
      (node (ref "RPI-CM1") (pin "128") (pinfunction "CAM0_D0_N_128") (pintype "passive"))
    )
    (net (code "102") (name "unconnected-(RPI-CM1B-CAM0_D0_P-Pad130)") (class "Default")
      (node (ref "RPI-CM1") (pin "130") (pinfunction "CAM0_D0_P_130") (pintype "passive"))
    )
    (net (code "103") (name "unconnected-(RPI-CM1B-CAM0_D1_N-Pad134)") (class "Default")
      (node (ref "RPI-CM1") (pin "134") (pinfunction "CAM0_D1_N_134") (pintype "passive"))
    )
    (net (code "104") (name "unconnected-(RPI-CM1B-CAM0_D1_P-Pad136)") (class "Default")
      (node (ref "RPI-CM1") (pin "136") (pinfunction "CAM0_D1_P_136") (pintype "passive"))
    )
    (net (code "105") (name "unconnected-(RPI-CM1B-CAM1_C_N-Pad127)") (class "Default")
      (node (ref "RPI-CM1") (pin "127") (pinfunction "CAM1_C_N_127") (pintype "passive"))
    )
    (net (code "106") (name "unconnected-(RPI-CM1B-CAM1_C_P-Pad129)") (class "Default")
      (node (ref "RPI-CM1") (pin "129") (pinfunction "CAM1_C_P_129") (pintype "passive"))
    )
    (net (code "107") (name "unconnected-(RPI-CM1B-CAM1_D0_N-Pad115)") (class "Default")
      (node (ref "RPI-CM1") (pin "115") (pinfunction "CAM1_D0_N_115") (pintype "passive"))
    )
    (net (code "108") (name "unconnected-(RPI-CM1B-CAM1_D0_P-Pad117)") (class "Default")
      (node (ref "RPI-CM1") (pin "117") (pinfunction "CAM1_D0_P_117") (pintype "passive"))
    )
    (net (code "109") (name "unconnected-(RPI-CM1B-CAM1_D1_N-Pad121)") (class "Default")
      (node (ref "RPI-CM1") (pin "121") (pinfunction "CAM1_D1_N_121") (pintype "passive"))
    )
    (net (code "110") (name "unconnected-(RPI-CM1B-CAM1_D1_P-Pad123)") (class "Default")
      (node (ref "RPI-CM1") (pin "123") (pinfunction "CAM1_D1_P_123") (pintype "passive"))
    )
    (net (code "111") (name "unconnected-(RPI-CM1B-CAM1_D2_N-Pad133)") (class "Default")
      (node (ref "RPI-CM1") (pin "133") (pinfunction "CAM1_D2_N_133") (pintype "passive"))
    )
    (net (code "112") (name "unconnected-(RPI-CM1B-CAM1_D2_P-Pad135)") (class "Default")
      (node (ref "RPI-CM1") (pin "135") (pinfunction "CAM1_D2_P_135") (pintype "passive"))
    )
    (net (code "113") (name "unconnected-(RPI-CM1B-CAM1_D3_N-Pad139)") (class "Default")
      (node (ref "RPI-CM1") (pin "139") (pinfunction "CAM1_D3_N_139") (pintype "passive"))
    )
    (net (code "114") (name "unconnected-(RPI-CM1B-CAM1_D3_P-Pad141)") (class "Default")
      (node (ref "RPI-CM1") (pin "141") (pinfunction "CAM1_D3_P_141") (pintype "passive"))
    )
    (net (code "115") (name "unconnected-(RPI-CM1B-DSI0_C_N-Pad169)") (class "Default")
      (node (ref "RPI-CM1") (pin "169") (pinfunction "DSI0_C_N_169") (pintype "passive"))
    )
    (net (code "116") (name "unconnected-(RPI-CM1B-DSI0_C_P-Pad171)") (class "Default")
      (node (ref "RPI-CM1") (pin "171") (pinfunction "DSI0_C_P_171") (pintype "passive"))
    )
    (net (code "117") (name "unconnected-(RPI-CM1B-DSI0_D0_N-Pad157)") (class "Default")
      (node (ref "RPI-CM1") (pin "157") (pinfunction "DSI0_D0_N_157") (pintype "passive"))
    )
    (net (code "118") (name "unconnected-(RPI-CM1B-DSI0_D0_P-Pad159)") (class "Default")
      (node (ref "RPI-CM1") (pin "159") (pinfunction "DSI0_D0_P_159") (pintype "passive"))
    )
    (net (code "119") (name "unconnected-(RPI-CM1B-DSI0_D1_N-Pad163)") (class "Default")
      (node (ref "RPI-CM1") (pin "163") (pinfunction "DSI0_D1_N_163") (pintype "passive"))
    )
    (net (code "120") (name "unconnected-(RPI-CM1B-DSI0_D1_P-Pad165)") (class "Default")
      (node (ref "RPI-CM1") (pin "165") (pinfunction "DSI0_D1_P_165") (pintype "passive"))
    )
    (net (code "121") (name "unconnected-(RPI-CM1B-DSI1_C_N-Pad187)") (class "Default")
      (node (ref "RPI-CM1") (pin "187") (pinfunction "DSI1_C_N_187") (pintype "passive"))
    )
    (net (code "122") (name "unconnected-(RPI-CM1B-DSI1_C_P-Pad189)") (class "Default")
      (node (ref "RPI-CM1") (pin "189") (pinfunction "DSI1_C_P_189") (pintype "passive"))
    )
    (net (code "123") (name "unconnected-(RPI-CM1B-DSI1_D0_N-Pad175)") (class "Default")
      (node (ref "RPI-CM1") (pin "175") (pinfunction "DSI1_D0_N_175") (pintype "passive"))
    )
    (net (code "124") (name "unconnected-(RPI-CM1B-DSI1_D0_P-Pad177)") (class "Default")
      (node (ref "RPI-CM1") (pin "177") (pinfunction "DSI1_D0_P_177") (pintype "passive"))
    )
    (net (code "125") (name "unconnected-(RPI-CM1B-DSI1_D1_N-Pad181)") (class "Default")
      (node (ref "RPI-CM1") (pin "181") (pinfunction "DSI1_D1_N_181") (pintype "passive"))
    )
    (net (code "126") (name "unconnected-(RPI-CM1B-DSI1_D1_P-Pad183)") (class "Default")
      (node (ref "RPI-CM1") (pin "183") (pinfunction "DSI1_D1_P_183") (pintype "passive"))
    )
    (net (code "127") (name "unconnected-(RPI-CM1B-DSI1_D2_N-Pad193)") (class "Default")
      (node (ref "RPI-CM1") (pin "193") (pinfunction "DSI1_D2_N_193") (pintype "passive"))
    )
    (net (code "128") (name "unconnected-(RPI-CM1B-DSI1_D2_P-Pad195)") (class "Default")
      (node (ref "RPI-CM1") (pin "195") (pinfunction "DSI1_D2_P_195") (pintype "passive"))
    )
    (net (code "129") (name "unconnected-(RPI-CM1B-DSI1_D3_N-Pad194)") (class "Default")
      (node (ref "RPI-CM1") (pin "194") (pinfunction "DSI1_D3_N_194") (pintype "passive"))
    )
    (net (code "130") (name "unconnected-(RPI-CM1B-DSI1_D3_P-Pad196)") (class "Default")
      (node (ref "RPI-CM1") (pin "196") (pinfunction "DSI1_D3_P_196") (pintype "passive"))
    )
    (net (code "131") (name "unconnected-(RPI-CM1B-HDMI0_CEC-Pad151)") (class "Default")
      (node (ref "RPI-CM1") (pin "151") (pinfunction "HDMI0_CEC_151") (pintype "passive"))
    )
    (net (code "132") (name "unconnected-(RPI-CM1B-HDMI0_CLK_N-Pad190)") (class "Default")
      (node (ref "RPI-CM1") (pin "190") (pinfunction "HDMI0_CLK_N_190") (pintype "passive"))
    )
    (net (code "133") (name "unconnected-(RPI-CM1B-HDMI0_CLK_P-Pad188)") (class "Default")
      (node (ref "RPI-CM1") (pin "188") (pinfunction "HDMI0_CLK_P_188") (pintype "passive"))
    )
    (net (code "134") (name "unconnected-(RPI-CM1B-HDMI0_HOTPLUG-Pad153)") (class "Default")
      (node (ref "RPI-CM1") (pin "153") (pinfunction "HDMI0_HOTPLUG_153") (pintype "passive"))
    )
    (net (code "135") (name "unconnected-(RPI-CM1B-HDMI0_SCL-Pad200)") (class "Default")
      (node (ref "RPI-CM1") (pin "200") (pinfunction "HDMI0_SCL_200") (pintype "passive"))
    )
    (net (code "136") (name "unconnected-(RPI-CM1B-HDMI0_SDA-Pad199)") (class "Default")
      (node (ref "RPI-CM1") (pin "199") (pinfunction "HDMI0_SDA_199") (pintype "passive"))
    )
    (net (code "137") (name "unconnected-(RPI-CM1B-HDMI0_TX0_N-Pad184)") (class "Default")
      (node (ref "RPI-CM1") (pin "184") (pinfunction "HDMI0_TX0_N_184") (pintype "passive"))
    )
    (net (code "138") (name "unconnected-(RPI-CM1B-HDMI0_TX0_P-Pad182)") (class "Default")
      (node (ref "RPI-CM1") (pin "182") (pinfunction "HDMI0_TX0_P_182") (pintype "passive"))
    )
    (net (code "139") (name "unconnected-(RPI-CM1B-HDMI0_TX1_N-Pad178)") (class "Default")
      (node (ref "RPI-CM1") (pin "178") (pinfunction "HDMI0_TX1_N_178") (pintype "passive"))
    )
    (net (code "140") (name "unconnected-(RPI-CM1B-HDMI0_TX1_P-Pad176)") (class "Default")
      (node (ref "RPI-CM1") (pin "176") (pinfunction "HDMI0_TX1_P_176") (pintype "passive"))
    )
    (net (code "141") (name "unconnected-(RPI-CM1B-HDMI0_TX2_N-Pad172)") (class "Default")
      (node (ref "RPI-CM1") (pin "172") (pinfunction "HDMI0_TX2_N_172") (pintype "passive"))
    )
    (net (code "142") (name "unconnected-(RPI-CM1B-HDMI0_TX2_P-Pad170)") (class "Default")
      (node (ref "RPI-CM1") (pin "170") (pinfunction "HDMI0_TX2_P_170") (pintype "passive"))
    )
    (net (code "143") (name "unconnected-(RPI-CM1B-HDMI1_CEC-Pad149)") (class "Default")
      (node (ref "RPI-CM1") (pin "149") (pinfunction "HDMI1_CEC_149") (pintype "passive"))
    )
    (net (code "144") (name "unconnected-(RPI-CM1B-HDMI1_CLK_N-Pad166)") (class "Default")
      (node (ref "RPI-CM1") (pin "166") (pinfunction "HDMI1_CLK_N_166") (pintype "passive"))
    )
    (net (code "145") (name "unconnected-(RPI-CM1B-HDMI1_CLK_P-Pad164)") (class "Default")
      (node (ref "RPI-CM1") (pin "164") (pinfunction "HDMI1_CLK_P_164") (pintype "passive"))
    )
    (net (code "146") (name "unconnected-(RPI-CM1B-HDMI1_HOTPLUG-Pad143)") (class "Default")
      (node (ref "RPI-CM1") (pin "143") (pinfunction "HDMI1_HOTPLUG_143") (pintype "passive"))
    )
    (net (code "147") (name "unconnected-(RPI-CM1B-HDMI1_SCL-Pad147)") (class "Default")
      (node (ref "RPI-CM1") (pin "147") (pinfunction "HDMI1_SCL_147") (pintype "passive"))
    )
    (net (code "148") (name "unconnected-(RPI-CM1B-HDMI1_SDA-Pad145)") (class "Default")
      (node (ref "RPI-CM1") (pin "145") (pinfunction "HDMI1_SDA_145") (pintype "passive"))
    )
    (net (code "149") (name "unconnected-(RPI-CM1B-HDMI1_TX0_N-Pad160)") (class "Default")
      (node (ref "RPI-CM1") (pin "160") (pinfunction "HDMI1_TX0_N_160") (pintype "passive"))
    )
    (net (code "150") (name "unconnected-(RPI-CM1B-HDMI1_TX0_P-Pad158)") (class "Default")
      (node (ref "RPI-CM1") (pin "158") (pinfunction "HDMI1_TX0_P_158") (pintype "passive"))
    )
    (net (code "151") (name "unconnected-(RPI-CM1B-HDMI1_TX1_N-Pad154)") (class "Default")
      (node (ref "RPI-CM1") (pin "154") (pinfunction "HDMI1_TX1_N_154") (pintype "passive"))
    )
    (net (code "152") (name "unconnected-(RPI-CM1B-HDMI1_TX1_P-Pad152)") (class "Default")
      (node (ref "RPI-CM1") (pin "152") (pinfunction "HDMI1_TX1_P_152") (pintype "passive"))
    )
    (net (code "153") (name "unconnected-(RPI-CM1B-HDMI1_TX2_N-Pad148)") (class "Default")
      (node (ref "RPI-CM1") (pin "148") (pinfunction "HDMI1_TX2_N_148") (pintype "passive"))
    )
    (net (code "154") (name "unconnected-(RPI-CM1B-HDMI1_TX2_P-Pad146)") (class "Default")
      (node (ref "RPI-CM1") (pin "146") (pinfunction "HDMI1_TX2_P_146") (pintype "passive"))
    )
    (net (code "155") (name "unconnected-(RPI-CM1B-RESERVED-Pad104)") (class "Default")
      (node (ref "RPI-CM1") (pin "104") (pinfunction "RESERVED_104") (pintype "passive"))
    )
    (net (code "156") (name "unconnected-(RPI-CM1B-RESERVED-Pad106)") (class "Default")
      (node (ref "RPI-CM1") (pin "106") (pinfunction "RESERVED_106") (pintype "passive"))
    )
    (net (code "157") (name "unconnected-(RPI-CM1B-VDAC_COMP-Pad111)") (class "Default")
      (node (ref "RPI-CM1") (pin "111") (pinfunction "VDAC_COMP_111") (pintype "passive"))
    )
  )
)
